# as14120_fpga_power_conf.net
KiCad netlist of a schematic drawn in Altium Designer
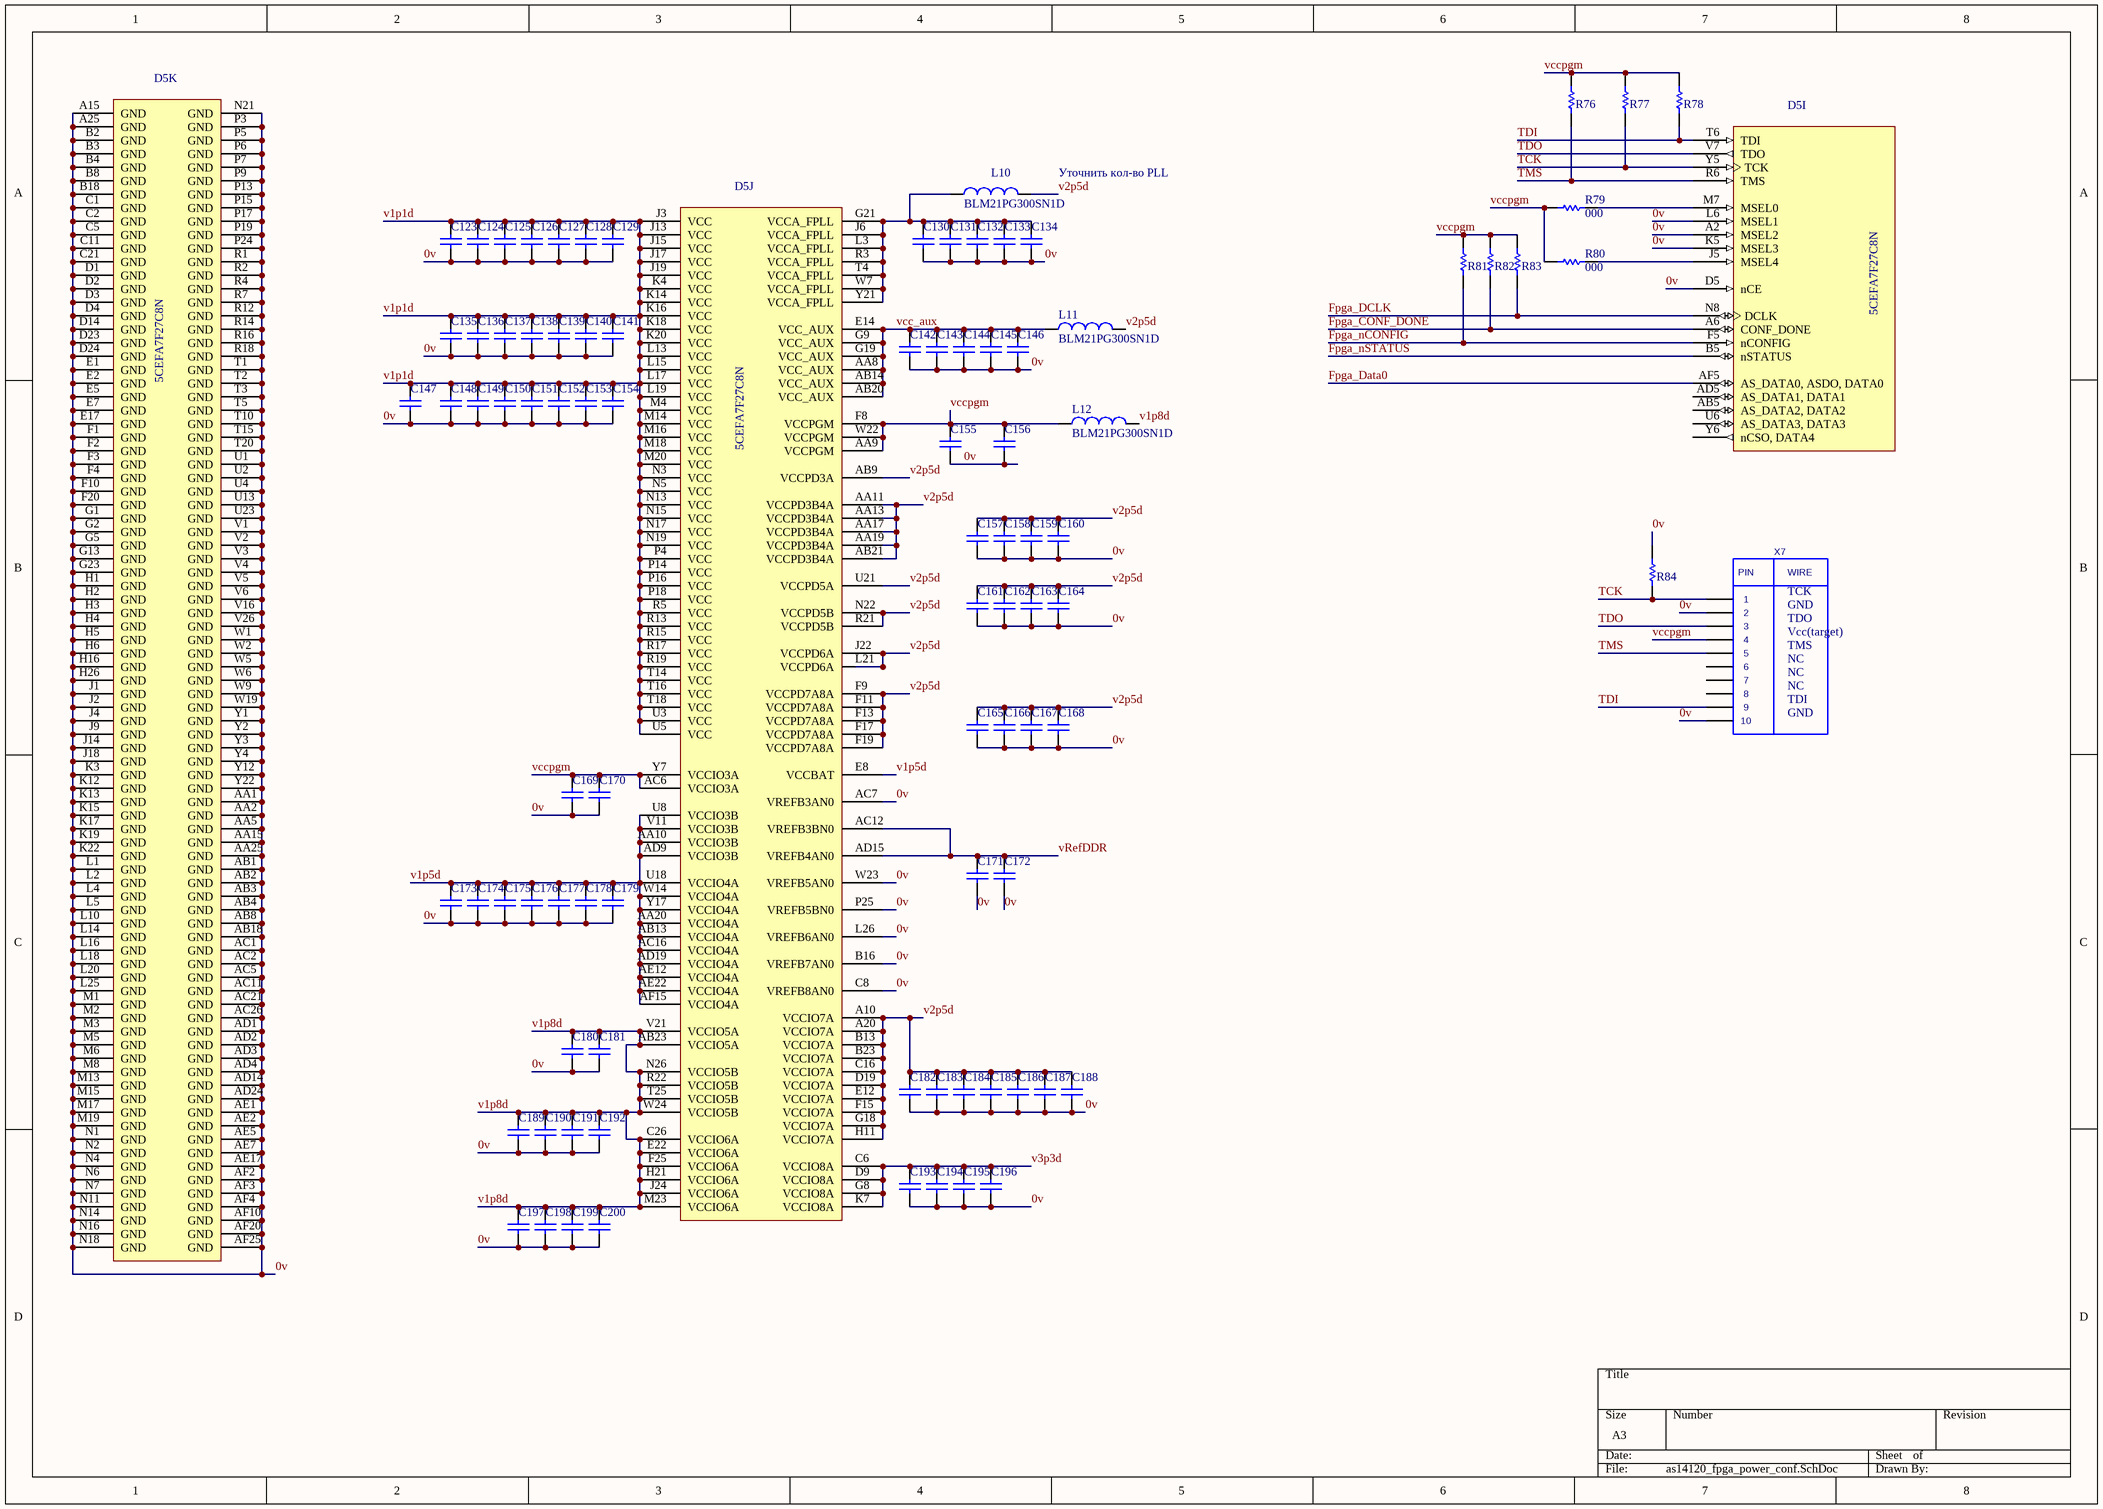
[diagram p0: as14120_fpga_power_conf.SchDoc]

(export (version "E")
  (design (tool "Eeschema 10.0.6"))
  (components
    (comp (ref "C123")
      (value "CAP 1uF 10V 0402(1005)")
      (footprint "CAPC0402(1005)60_M")
      (description "CAP 1uF 10V ±20% 0402 (1005 Metric) Thickness 0.6mm SMD")
      (fields (field (name "TOLERANCE") "±20%"))
      (libsource (lib "as14120") (part "CAP_0402"))
    )
    (comp (ref "C124")
      (value "CAP 1uF 10V 0402(1005)")
      (footprint "CAPC0402(1005)60_M")
      (description "CAP 1uF 10V ±20% 0402 (1005 Metric) Thickness 0.6mm SMD")
      (fields (field (name "TOLERANCE") "±20%"))
      (libsource (lib "as14120") (part "CAP_0402"))
    )
    (comp (ref "C125")
      (value "CAP 1uF 10V 0402(1005)")
      (footprint "CAPC0402(1005)60_M")
      (description "CAP 1uF 10V ±20% 0402 (1005 Metric) Thickness 0.6mm SMD")
      (fields (field (name "TOLERANCE") "±20%"))
      (libsource (lib "as14120") (part "CAP_0402"))
    )
    (comp (ref "C126")
      (value "CAP 1uF 10V 0402(1005)")
      (footprint "CAPC0402(1005)60_M")
      (description "CAP 1uF 10V ±20% 0402 (1005 Metric) Thickness 0.6mm SMD")
      (fields (field (name "TOLERANCE") "±20%"))
      (libsource (lib "as14120") (part "CAP_0402"))
    )
    (comp (ref "C127")
      (value "CAP 1uF 10V 0402(1005)")
      (footprint "CAPC0402(1005)60_M")
      (description "CAP 1uF 10V ±20% 0402 (1005 Metric) Thickness 0.6mm SMD")
      (fields (field (name "TOLERANCE") "±20%"))
      (libsource (lib "as14120") (part "CAP_0402"))
    )
    (comp (ref "C128")
      (value "CAP 1uF 10V 0402(1005)")
      (footprint "CAPC0402(1005)60_M")
      (description "CAP 1uF 10V ±20% 0402 (1005 Metric) Thickness 0.6mm SMD")
      (fields (field (name "TOLERANCE") "±20%"))
      (libsource (lib "as14120") (part "CAP_0402"))
    )
    (comp (ref "C129")
      (value "CAP 1uF 10V 0402(1005)")
      (footprint "CAPC0402(1005)60_M")
      (description "CAP 1uF 10V ±20% 0402 (1005 Metric) Thickness 0.6mm SMD")
      (fields (field (name "TOLERANCE") "±20%"))
      (libsource (lib "as14120") (part "CAP_0402"))
    )
    (comp (ref "C130")
      (value "CAP 1uF 10V 0402(1005)")
      (footprint "CAPC0402(1005)60_M")
      (description "CAP 1uF 10V ±20% 0402 (1005 Metric) Thickness 0.6mm SMD")
      (fields (field (name "TOLERANCE") "±20%"))
      (libsource (lib "as14120") (part "CAP_0402"))
    )
    (comp (ref "C131")
      (value "CAP 1uF 10V 0402(1005)")
      (footprint "CAPC0402(1005)60_M")
      (description "CAP 1uF 10V ±20% 0402 (1005 Metric) Thickness 0.6mm SMD")
      (fields (field (name "TOLERANCE") "±20%"))
      (libsource (lib "as14120") (part "CAP_0402"))
    )
    (comp (ref "C132")
      (value "CAP 1uF 10V 0402(1005)")
      (footprint "CAPC0402(1005)60_M")
      (description "CAP 1uF 10V ±20% 0402 (1005 Metric) Thickness 0.6mm SMD")
      (fields (field (name "TOLERANCE") "±20%"))
      (libsource (lib "as14120") (part "CAP_0402"))
    )
    (comp (ref "C133")
      (value "CAP 1uF 10V 0402(1005)")
      (footprint "CAPC0402(1005)60_M")
      (description "CAP 1uF 10V ±20% 0402 (1005 Metric) Thickness 0.6mm SMD")
      (fields (field (name "TOLERANCE") "±20%"))
      (libsource (lib "as14120") (part "CAP_0402"))
    )
    (comp (ref "C134")
      (value "CAP 1uF 10V 0402(1005)")
      (footprint "CAPC0402(1005)60_M")
      (description "CAP 1uF 10V ±20% 0402 (1005 Metric) Thickness 0.6mm SMD")
      (fields (field (name "TOLERANCE") "±20%"))
      (libsource (lib "as14120") (part "CAP_0402"))
    )
    (comp (ref "C135")
      (value "CAP 1uF 10V 0402(1005)")
      (footprint "CAPC0402(1005)60_M")
      (description "CAP 1uF 10V ±20% 0402 (1005 Metric) Thickness 0.6mm SMD")
      (fields (field (name "TOLERANCE") "±20%"))
      (libsource (lib "as14120") (part "CAP_0402"))
    )
    (comp (ref "C136")
      (value "CAP 1uF 10V 0402(1005)")
      (footprint "CAPC0402(1005)60_M")
      (description "CAP 1uF 10V ±20% 0402 (1005 Metric) Thickness 0.6mm SMD")
      (fields (field (name "TOLERANCE") "±20%"))
      (libsource (lib "as14120") (part "CAP_0402"))
    )
    (comp (ref "C137")
      (value "CAP 1uF 10V 0402(1005)")
      (footprint "CAPC0402(1005)60_M")
      (description "CAP 1uF 10V ±20% 0402 (1005 Metric) Thickness 0.6mm SMD")
      (fields (field (name "TOLERANCE") "±20%"))
      (libsource (lib "as14120") (part "CAP_0402"))
    )
    (comp (ref "C138")
      (value "CAP 1uF 10V 0402(1005)")
      (footprint "CAPC0402(1005)60_M")
      (description "CAP 1uF 10V ±20% 0402 (1005 Metric) Thickness 0.6mm SMD")
      (fields (field (name "TOLERANCE") "±20%"))
      (libsource (lib "as14120") (part "CAP_0402"))
    )
    (comp (ref "C139")
      (value "CAP 1uF 10V 0402(1005)")
      (footprint "CAPC0402(1005)60_M")
      (description "CAP 1uF 10V ±20% 0402 (1005 Metric) Thickness 0.6mm SMD")
      (fields (field (name "TOLERANCE") "±20%"))
      (libsource (lib "as14120") (part "CAP_0402"))
    )
    (comp (ref "C140")
      (value "CAP 1uF 10V 0402(1005)")
      (footprint "CAPC0402(1005)60_M")
      (description "CAP 1uF 10V ±20% 0402 (1005 Metric) Thickness 0.6mm SMD")
      (fields (field (name "TOLERANCE") "±20%"))
      (libsource (lib "as14120") (part "CAP_0402"))
    )
    (comp (ref "C141")
      (value "CAP 1uF 10V 0402(1005)")
      (footprint "CAPC0402(1005)60_M")
      (description "CAP 1uF 10V ±20% 0402 (1005 Metric) Thickness 0.6mm SMD")
      (fields (field (name "TOLERANCE") "±20%"))
      (libsource (lib "as14120") (part "CAP_0402"))
    )
    (comp (ref "C142")
      (value "CAP 1uF 10V 0402(1005)")
      (footprint "CAPC0402(1005)60_M")
      (description "CAP 1uF 10V ±20% 0402 (1005 Metric) Thickness 0.6mm SMD")
      (fields (field (name "TOLERANCE") "±20%"))
      (libsource (lib "as14120") (part "CAP_0402"))
    )
    (comp (ref "C143")
      (value "CAP 1uF 10V 0402(1005)")
      (footprint "CAPC0402(1005)60_M")
      (description "CAP 1uF 10V ±20% 0402 (1005 Metric) Thickness 0.6mm SMD")
      (fields (field (name "TOLERANCE") "±20%"))
      (libsource (lib "as14120") (part "CAP_0402"))
    )
    (comp (ref "C144")
      (value "CAP 1uF 10V 0402(1005)")
      (footprint "CAPC0402(1005)60_M")
      (description "CAP 1uF 10V ±20% 0402 (1005 Metric) Thickness 0.6mm SMD")
      (fields (field (name "TOLERANCE") "±20%"))
      (libsource (lib "as14120") (part "CAP_0402"))
    )
    (comp (ref "C145")
      (value "CAP 1uF 10V 0402(1005)")
      (footprint "CAPC0402(1005)60_M")
      (description "CAP 1uF 10V ±20% 0402 (1005 Metric) Thickness 0.6mm SMD")
      (fields (field (name "TOLERANCE") "±20%"))
      (libsource (lib "as14120") (part "CAP_0402"))
    )
    (comp (ref "C146")
      (value "CAP 1uF 10V 0402(1005)")
      (footprint "CAPC0402(1005)60_M")
      (description "CAP 1uF 10V ±20% 0402 (1005 Metric) Thickness 0.6mm SMD")
      (fields (field (name "TOLERANCE") "±20%"))
      (libsource (lib "as14120") (part "CAP_0402"))
    )
    (comp (ref "C147")
      (value "CAP 1uF 10V 0402(1005)")
      (footprint "CAPC0402(1005)60_M")
      (description "CAP 1uF 10V ±20% 0402 (1005 Metric) Thickness 0.6mm SMD")
      (fields (field (name "TOLERANCE") "±20%"))
      (libsource (lib "as14120") (part "CAP_0402"))
    )
    (comp (ref "C148")
      (value "CAP 1uF 10V 0402(1005)")
      (footprint "CAPC0402(1005)60_M")
      (description "CAP 1uF 10V ±20% 0402 (1005 Metric) Thickness 0.6mm SMD")
      (fields (field (name "TOLERANCE") "±20%"))
      (libsource (lib "as14120") (part "CAP_0402"))
    )
    (comp (ref "C149")
      (value "CAP 1uF 10V 0402(1005)")
      (footprint "CAPC0402(1005)60_M")
      (description "CAP 1uF 10V ±20% 0402 (1005 Metric) Thickness 0.6mm SMD")
      (fields (field (name "TOLERANCE") "±20%"))
      (libsource (lib "as14120") (part "CAP_0402"))
    )
    (comp (ref "C150")
      (value "CAP 1uF 10V 0402(1005)")
      (footprint "CAPC0402(1005)60_M")
      (description "CAP 1uF 10V ±20% 0402 (1005 Metric) Thickness 0.6mm SMD")
      (fields (field (name "TOLERANCE") "±20%"))
      (libsource (lib "as14120") (part "CAP_0402"))
    )
    (comp (ref "C151")
      (value "CAP 1uF 10V 0402(1005)")
      (footprint "CAPC0402(1005)60_M")
      (description "CAP 1uF 10V ±20% 0402 (1005 Metric) Thickness 0.6mm SMD")
      (fields (field (name "TOLERANCE") "±20%"))
      (libsource (lib "as14120") (part "CAP_0402"))
    )
    (comp (ref "C152")
      (value "CAP 1uF 10V 0402(1005)")
      (footprint "CAPC0402(1005)60_M")
      (description "CAP 1uF 10V ±20% 0402 (1005 Metric) Thickness 0.6mm SMD")
      (fields (field (name "TOLERANCE") "±20%"))
      (libsource (lib "as14120") (part "CAP_0402"))
    )
    (comp (ref "C153")
      (value "CAP 1uF 10V 0402(1005)")
      (footprint "CAPC0402(1005)60_M")
      (description "CAP 1uF 10V ±20% 0402 (1005 Metric) Thickness 0.6mm SMD")
      (fields (field (name "TOLERANCE") "±20%"))
      (libsource (lib "as14120") (part "CAP_0402"))
    )
    (comp (ref "C154")
      (value "CAP 1uF 10V 0402(1005)")
      (footprint "CAPC0402(1005)60_M")
      (description "CAP 1uF 10V ±20% 0402 (1005 Metric) Thickness 0.6mm SMD")
      (fields (field (name "TOLERANCE") "±20%"))
      (libsource (lib "as14120") (part "CAP_0402"))
    )
    (comp (ref "C155")
      (value "CAP 1uF 10V 0402(1005)")
      (footprint "CAPC0402(1005)60_M")
      (description "CAP 1uF 10V ±20% 0402 (1005 Metric) Thickness 0.6mm SMD")
      (fields (field (name "TOLERANCE") "±20%"))
      (libsource (lib "as14120") (part "CAP_0402"))
    )
    (comp (ref "C156")
      (value "CAP 1uF 10V 0402(1005)")
      (footprint "CAPC0402(1005)60_M")
      (description "CAP 1uF 10V ±20% 0402 (1005 Metric) Thickness 0.6mm SMD")
      (fields (field (name "TOLERANCE") "±20%"))
      (libsource (lib "as14120") (part "CAP_0402"))
    )
    (comp (ref "C157")
      (value "CAP 1uF 10V 0402(1005)")
      (footprint "CAPC0402(1005)60_M")
      (description "CAP 1uF 10V ±20% 0402 (1005 Metric) Thickness 0.6mm SMD")
      (fields (field (name "TOLERANCE") "±20%"))
      (libsource (lib "as14120") (part "CAP_0402"))
    )
    (comp (ref "C158")
      (value "CAP 1uF 10V 0402(1005)")
      (footprint "CAPC0402(1005)60_M")
      (description "CAP 1uF 10V ±20% 0402 (1005 Metric) Thickness 0.6mm SMD")
      (fields (field (name "TOLERANCE") "±20%"))
      (libsource (lib "as14120") (part "CAP_0402"))
    )
    (comp (ref "C159")
      (value "CAP 1uF 10V 0402(1005)")
      (footprint "CAPC0402(1005)60_M")
      (description "CAP 1uF 10V ±20% 0402 (1005 Metric) Thickness 0.6mm SMD")
      (fields (field (name "TOLERANCE") "±20%"))
      (libsource (lib "as14120") (part "CAP_0402"))
    )
    (comp (ref "C160")
      (value "CAP 1uF 10V 0402(1005)")
      (footprint "CAPC0402(1005)60_M")
      (description "CAP 1uF 10V ±20% 0402 (1005 Metric) Thickness 0.6mm SMD")
      (fields (field (name "TOLERANCE") "±20%"))
      (libsource (lib "as14120") (part "CAP_0402"))
    )
    (comp (ref "C161")
      (value "CAP 1uF 10V 0402(1005)")
      (footprint "CAPC0402(1005)60_M")
      (description "CAP 1uF 10V ±20% 0402 (1005 Metric) Thickness 0.6mm SMD")
      (fields (field (name "TOLERANCE") "±20%"))
      (libsource (lib "as14120") (part "CAP_0402"))
    )
    (comp (ref "C162")
      (value "CAP 1uF 10V 0402(1005)")
      (footprint "CAPC0402(1005)60_M")
      (description "CAP 1uF 10V ±20% 0402 (1005 Metric) Thickness 0.6mm SMD")
      (fields (field (name "TOLERANCE") "±20%"))
      (libsource (lib "as14120") (part "CAP_0402"))
    )
    (comp (ref "C163")
      (value "CAP 1uF 10V 0402(1005)")
      (footprint "CAPC0402(1005)60_M")
      (description "CAP 1uF 10V ±20% 0402 (1005 Metric) Thickness 0.6mm SMD")
      (fields (field (name "TOLERANCE") "±20%"))
      (libsource (lib "as14120") (part "CAP_0402"))
    )
    (comp (ref "C164")
      (value "CAP 1uF 10V 0402(1005)")
      (footprint "CAPC0402(1005)60_M")
      (description "CAP 1uF 10V ±20% 0402 (1005 Metric) Thickness 0.6mm SMD")
      (fields (field (name "TOLERANCE") "±20%"))
      (libsource (lib "as14120") (part "CAP_0402"))
    )
    (comp (ref "C165")
      (value "CAP 1uF 10V 0402(1005)")
      (footprint "CAPC0402(1005)60_M")
      (description "CAP 1uF 10V ±20% 0402 (1005 Metric) Thickness 0.6mm SMD")
      (fields (field (name "TOLERANCE") "±20%"))
      (libsource (lib "as14120") (part "CAP_0402"))
    )
    (comp (ref "C166")
      (value "CAP 1uF 10V 0402(1005)")
      (footprint "CAPC0402(1005)60_M")
      (description "CAP 1uF 10V ±20% 0402 (1005 Metric) Thickness 0.6mm SMD")
      (fields (field (name "TOLERANCE") "±20%"))
      (libsource (lib "as14120") (part "CAP_0402"))
    )
    (comp (ref "C167")
      (value "CAP 1uF 10V 0402(1005)")
      (footprint "CAPC0402(1005)60_M")
      (description "CAP 1uF 10V ±20% 0402 (1005 Metric) Thickness 0.6mm SMD")
      (fields (field (name "TOLERANCE") "±20%"))
      (libsource (lib "as14120") (part "CAP_0402"))
    )
    (comp (ref "C168")
      (value "CAP 1uF 10V 0402(1005)")
      (footprint "CAPC0402(1005)60_M")
      (description "CAP 1uF 10V ±20% 0402 (1005 Metric) Thickness 0.6mm SMD")
      (fields (field (name "TOLERANCE") "±20%"))
      (libsource (lib "as14120") (part "CAP_0402"))
    )
    (comp (ref "C169")
      (value "CAP 1uF 10V 0402(1005)")
      (footprint "CAPC0402(1005)60_M")
      (description "CAP 1uF 10V ±20% 0402 (1005 Metric) Thickness 0.6mm SMD")
      (fields (field (name "TOLERANCE") "±20%"))
      (libsource (lib "as14120") (part "CAP_0402"))
    )
    (comp (ref "C170")
      (value "CAP 1uF 10V 0402(1005)")
      (footprint "CAPC0402(1005)60_M")
      (description "CAP 1uF 10V ±20% 0402 (1005 Metric) Thickness 0.6mm SMD")
      (fields (field (name "TOLERANCE") "±20%"))
      (libsource (lib "as14120") (part "CAP_0402"))
    )
    (comp (ref "C171")
      (value "CAP 1uF 10V 0402(1005)")
      (footprint "CAPC0402(1005)60_M")
      (description "CAP 1uF 10V ±20% 0402 (1005 Metric) Thickness 0.6mm SMD")
      (fields (field (name "TOLERANCE") "±20%"))
      (libsource (lib "as14120") (part "CAP_0402"))
    )
    (comp (ref "C172")
      (value "CAP 1uF 10V 0402(1005)")
      (footprint "CAPC0402(1005)60_M")
      (description "CAP 1uF 10V ±20% 0402 (1005 Metric) Thickness 0.6mm SMD")
      (fields (field (name "TOLERANCE") "±20%"))
      (libsource (lib "as14120") (part "CAP_0402"))
    )
    (comp (ref "C173")
      (value "CAP 1uF 10V 0402(1005)")
      (footprint "CAPC0402(1005)60_M")
      (description "CAP 1uF 10V ±20% 0402 (1005 Metric) Thickness 0.6mm SMD")
      (fields (field (name "TOLERANCE") "±20%"))
      (libsource (lib "as14120") (part "CAP_0402"))
    )
    (comp (ref "C174")
      (value "CAP 1uF 10V 0402(1005)")
      (footprint "CAPC0402(1005)60_M")
      (description "CAP 1uF 10V ±20% 0402 (1005 Metric) Thickness 0.6mm SMD")
      (fields (field (name "TOLERANCE") "±20%"))
      (libsource (lib "as14120") (part "CAP_0402"))
    )
    (comp (ref "C175")
      (value "CAP 1uF 10V 0402(1005)")
      (footprint "CAPC0402(1005)60_M")
      (description "CAP 1uF 10V ±20% 0402 (1005 Metric) Thickness 0.6mm SMD")
      (fields (field (name "TOLERANCE") "±20%"))
      (libsource (lib "as14120") (part "CAP_0402"))
    )
    (comp (ref "C176")
      (value "CAP 1uF 10V 0402(1005)")
      (footprint "CAPC0402(1005)60_M")
      (description "CAP 1uF 10V ±20% 0402 (1005 Metric) Thickness 0.6mm SMD")
      (fields (field (name "TOLERANCE") "±20%"))
      (libsource (lib "as14120") (part "CAP_0402"))
    )
    (comp (ref "C177")
      (value "CAP 1uF 10V 0402(1005)")
      (footprint "CAPC0402(1005)60_M")
      (description "CAP 1uF 10V ±20% 0402 (1005 Metric) Thickness 0.6mm SMD")
      (fields (field (name "TOLERANCE") "±20%"))
      (libsource (lib "as14120") (part "CAP_0402"))
    )
    (comp (ref "C178")
      (value "CAP 1uF 10V 0402(1005)")
      (footprint "CAPC0402(1005)60_M")
      (description "CAP 1uF 10V ±20% 0402 (1005 Metric) Thickness 0.6mm SMD")
      (fields (field (name "TOLERANCE") "±20%"))
      (libsource (lib "as14120") (part "CAP_0402"))
    )
    (comp (ref "C179")
      (value "CAP 1uF 10V 0402(1005)")
      (footprint "CAPC0402(1005)60_M")
      (description "CAP 1uF 10V ±20% 0402 (1005 Metric) Thickness 0.6mm SMD")
      (fields (field (name "TOLERANCE") "±20%"))
      (libsource (lib "as14120") (part "CAP_0402"))
    )
    (comp (ref "C180")
      (value "CAP 1uF 10V 0402(1005)")
      (footprint "CAPC0402(1005)60_M")
      (description "CAP 1uF 10V ±20% 0402 (1005 Metric) Thickness 0.6mm SMD")
      (fields (field (name "TOLERANCE") "±20%"))
      (libsource (lib "as14120") (part "CAP_0402"))
    )
    (comp (ref "C181")
      (value "CAP 1uF 10V 0402(1005)")
      (footprint "CAPC0402(1005)60_M")
      (description "CAP 1uF 10V ±20% 0402 (1005 Metric) Thickness 0.6mm SMD")
      (fields (field (name "TOLERANCE") "±20%"))
      (libsource (lib "as14120") (part "CAP_0402"))
    )
    (comp (ref "C182")
      (value "CAP 1uF 10V 0402(1005)")
      (footprint "CAPC0402(1005)60_M")
      (description "CAP 1uF 10V ±20% 0402 (1005 Metric) Thickness 0.6mm SMD")
      (fields (field (name "TOLERANCE") "±20%"))
      (libsource (lib "as14120") (part "CAP_0402"))
    )
    (comp (ref "C183")
      (value "CAP 1uF 10V 0402(1005)")
      (footprint "CAPC0402(1005)60_M")
      (description "CAP 1uF 10V ±20% 0402 (1005 Metric) Thickness 0.6mm SMD")
      (fields (field (name "TOLERANCE") "±20%"))
      (libsource (lib "as14120") (part "CAP_0402"))
    )
    (comp (ref "C184")
      (value "CAP 1uF 10V 0402(1005)")
      (footprint "CAPC0402(1005)60_M")
      (description "CAP 1uF 10V ±20% 0402 (1005 Metric) Thickness 0.6mm SMD")
      (fields (field (name "TOLERANCE") "±20%"))
      (libsource (lib "as14120") (part "CAP_0402"))
    )
    (comp (ref "C185")
      (value "CAP 1uF 10V 0402(1005)")
      (footprint "CAPC0402(1005)60_M")
      (description "CAP 1uF 10V ±20% 0402 (1005 Metric) Thickness 0.6mm SMD")
      (fields (field (name "TOLERANCE") "±20%"))
      (libsource (lib "as14120") (part "CAP_0402"))
    )
    (comp (ref "C186")
      (value "CAP 1uF 10V 0402(1005)")
      (footprint "CAPC0402(1005)60_M")
      (description "CAP 1uF 10V ±20% 0402 (1005 Metric) Thickness 0.6mm SMD")
      (fields (field (name "TOLERANCE") "±20%"))
      (libsource (lib "as14120") (part "CAP_0402"))
    )
    (comp (ref "C187")
      (value "CAP 1uF 10V 0402(1005)")
      (footprint "CAPC0402(1005)60_M")
      (description "CAP 1uF 10V ±20% 0402 (1005 Metric) Thickness 0.6mm SMD")
      (fields (field (name "TOLERANCE") "±20%"))
      (libsource (lib "as14120") (part "CAP_0402"))
    )
    (comp (ref "C188")
      (value "CAP 1uF 10V 0402(1005)")
      (footprint "CAPC0402(1005)60_M")
      (description "CAP 1uF 10V ±20% 0402 (1005 Metric) Thickness 0.6mm SMD")
      (fields (field (name "TOLERANCE") "±20%"))
      (libsource (lib "as14120") (part "CAP_0402"))
    )
    (comp (ref "C189")
      (value "CAP 1uF 10V 0402(1005)")
      (footprint "CAPC0402(1005)60_M")
      (description "CAP 1uF 10V ±20% 0402 (1005 Metric) Thickness 0.6mm SMD")
      (fields (field (name "TOLERANCE") "±20%"))
      (libsource (lib "as14120") (part "CAP_0402"))
    )
    (comp (ref "C190")
      (value "CAP 1uF 10V 0402(1005)")
      (footprint "CAPC0402(1005)60_M")
      (description "CAP 1uF 10V ±20% 0402 (1005 Metric) Thickness 0.6mm SMD")
      (fields (field (name "TOLERANCE") "±20%"))
      (libsource (lib "as14120") (part "CAP_0402"))
    )
    (comp (ref "C191")
      (value "CAP 1uF 10V 0402(1005)")
      (footprint "CAPC0402(1005)60_M")
      (description "CAP 1uF 10V ±20% 0402 (1005 Metric) Thickness 0.6mm SMD")
      (fields (field (name "TOLERANCE") "±20%"))
      (libsource (lib "as14120") (part "CAP_0402"))
    )
    (comp (ref "C192")
      (value "CAP 1uF 10V 0402(1005)")
      (footprint "CAPC0402(1005)60_M")
      (description "CAP 1uF 10V ±20% 0402 (1005 Metric) Thickness 0.6mm SMD")
      (fields (field (name "TOLERANCE") "±20%"))
      (libsource (lib "as14120") (part "CAP_0402"))
    )
    (comp (ref "C193")
      (value "CAP 1uF 10V 0402(1005)")
      (footprint "CAPC0402(1005)60_M")
      (description "CAP 1uF 10V ±20% 0402 (1005 Metric) Thickness 0.6mm SMD")
      (fields (field (name "TOLERANCE") "±20%"))
      (libsource (lib "as14120") (part "CAP_0402"))
    )
    (comp (ref "C194")
      (value "CAP 1uF 10V 0402(1005)")
      (footprint "CAPC0402(1005)60_M")
      (description "CAP 1uF 10V ±20% 0402 (1005 Metric) Thickness 0.6mm SMD")
      (fields (field (name "TOLERANCE") "±20%"))
      (libsource (lib "as14120") (part "CAP_0402"))
    )
    (comp (ref "C195")
      (value "CAP 1uF 10V 0402(1005)")
      (footprint "CAPC0402(1005)60_M")
      (description "CAP 1uF 10V ±20% 0402 (1005 Metric) Thickness 0.6mm SMD")
      (fields (field (name "TOLERANCE") "±20%"))
      (libsource (lib "as14120") (part "CAP_0402"))
    )
    (comp (ref "C196")
      (value "CAP 1uF 10V 0402(1005)")
      (footprint "CAPC0402(1005)60_M")
      (description "CAP 1uF 10V ±20% 0402 (1005 Metric) Thickness 0.6mm SMD")
      (fields (field (name "TOLERANCE") "±20%"))
      (libsource (lib "as14120") (part "CAP_0402"))
    )
    (comp (ref "C197")
      (value "CAP 1uF 10V 0402(1005)")
      (footprint "CAPC0402(1005)60_M")
      (description "CAP 1uF 10V ±20% 0402 (1005 Metric) Thickness 0.6mm SMD")
      (fields (field (name "TOLERANCE") "±20%"))
      (libsource (lib "as14120") (part "CAP_0402"))
    )
    (comp (ref "C198")
      (value "CAP 1uF 10V 0402(1005)")
      (footprint "CAPC0402(1005)60_M")
      (description "CAP 1uF 10V ±20% 0402 (1005 Metric) Thickness 0.6mm SMD")
      (fields (field (name "TOLERANCE") "±20%"))
      (libsource (lib "as14120") (part "CAP_0402"))
    )
    (comp (ref "C199")
      (value "CAP 1uF 10V 0402(1005)")
      (footprint "CAPC0402(1005)60_M")
      (description "CAP 1uF 10V ±20% 0402 (1005 Metric) Thickness 0.6mm SMD")
      (fields (field (name "TOLERANCE") "±20%"))
      (libsource (lib "as14120") (part "CAP_0402"))
    )
    (comp (ref "C200")
      (value "CAP 1uF 10V 0402(1005)")
      (footprint "CAPC0402(1005)60_M")
      (description "CAP 1uF 10V ±20% 0402 (1005 Metric) Thickness 0.6mm SMD")
      (fields (field (name "TOLERANCE") "±20%"))
      (libsource (lib "as14120") (part "CAP_0402"))
    )
    (comp (ref "D5")
      (value "5CEFA7F27C8N")
      (footprint "ALTR-672-FBGA-2000A")
      (fields (field (name "MANUFACTURER") "Altera"))
      (libsource (lib "Altera Cyclone V E") (part "5CEFA7F27C8N"))
    )
    (comp (ref "L10")
      (value "BLM21PG300SN1D")
      (footprint "CAPC0805(2012)100_N")
      (libsource (lib "as14120") (part "Ferrite_beat"))
    )
    (comp (ref "L11")
      (value "BLM21PG300SN1D")
      (footprint "CAPC0805(2012)100_N")
      (libsource (lib "as14120") (part "Ferrite_beat"))
    )
    (comp (ref "L12")
      (value "BLM21PG300SN1D")
      (footprint "CAPC0805(2012)100_N")
      (libsource (lib "as14120") (part "Ferrite_beat"))
    )
    (comp (ref "R76")
      (value "1K 5% 0603(1608)")
      (footprint "RESC0603(1608)_L")
      (description "1K 0.1W 5% 0603 (1608 Metric)  SMD")
      (fields (field (name "TOLERANCE") "5 %") (field (name "POWER") "0.1 W"))
      (libsource (lib "as14120") (part "RES_0603"))
    )
    (comp (ref "R77")
      (value "1K 5% 0603(1608)")
      (footprint "RESC0603(1608)_L")
      (description "1K 0.1W 5% 0603 (1608 Metric)  SMD")
      (fields (field (name "TOLERANCE") "5 %") (field (name "POWER") "0.1 W"))
      (libsource (lib "as14120") (part "RES_0603"))
    )
    (comp (ref "R78")
      (value "1K 5% 0603(1608)")
      (footprint "RESC0603(1608)_L")
      (description "1K 0.1W 5% 0603 (1608 Metric)  SMD")
      (fields (field (name "TOLERANCE") "5 %") (field (name "POWER") "0.1 W"))
      (libsource (lib "as14120") (part "RES_0603"))
    )
    (comp (ref "R79")
      (value "000")
      (footprint "RESC0603(1608)_L")
      (description "1K 0.1W 5% 0603 (1608 Metric)  SMD")
      (fields (field (name "TOLERANCE") "5 %") (field (name "POWER") "0.1 W"))
      (libsource (lib "as14120") (part "RES_0603"))
    )
    (comp (ref "R80")
      (value "000")
      (footprint "RESC0603(1608)_L")
      (description "1K 0.1W 5% 0603 (1608 Metric)  SMD")
      (fields (field (name "TOLERANCE") "5 %") (field (name "POWER") "0.1 W"))
      (libsource (lib "as14120") (part "RES_0603"))
    )
    (comp (ref "R81")
      (value "1K 5% 0603(1608)")
      (footprint "RESC0603(1608)_L")
      (description "1K 0.1W 5% 0603 (1608 Metric)  SMD")
      (fields (field (name "TOLERANCE") "5 %") (field (name "POWER") "0.1 W"))
      (libsource (lib "as14120") (part "RES_0603"))
    )
    (comp (ref "R82")
      (value "1K 5% 0603(1608)")
      (footprint "RESC0603(1608)_L")
      (description "1K 0.1W 5% 0603 (1608 Metric)  SMD")
      (fields (field (name "TOLERANCE") "5 %") (field (name "POWER") "0.1 W"))
      (libsource (lib "as14120") (part "RES_0603"))
    )
    (comp (ref "R83")
      (value "1K 5% 0603(1608)")
      (footprint "RESC0603(1608)_L")
      (description "1K 0.1W 5% 0603 (1608 Metric)  SMD")
      (fields (field (name "TOLERANCE") "5 %") (field (name "POWER") "0.1 W"))
      (libsource (lib "as14120") (part "RES_0603"))
    )
    (comp (ref "R84")
      (value "1K 5% 0603(1608)")
      (footprint "RESC0603(1608)_L")
      (description "1K 0.1W 5% 0603 (1608 Metric)  SMD")
      (fields (field (name "TOLERANCE") "5 %") (field (name "POWER") "0.1 W"))
      (libsource (lib "as14120") (part "RES_0603"))
    )
    (comp (ref "X7") (value "IDC10") (footprint "IDC10M") (libsource (lib "alexsb") (part "IDC10")))
  )
  (nets
    (net (code "1") (name "/0v") (class "Default")
      (node (ref "C123") (pin "1") (pinfunction "1_1") (pintype "passive"))
      (node (ref "C124") (pin "1") (pinfunction "1_1") (pintype "passive"))
      (node (ref "C125") (pin "1") (pinfunction "1_1") (pintype "passive"))
      (node (ref "C126") (pin "1") (pinfunction "1_1") (pintype "passive"))
      (node (ref "C127") (pin "1") (pinfunction "1_1") (pintype "passive"))
      (node (ref "C128") (pin "1") (pinfunction "1_1") (pintype "passive"))
      (node (ref "C129") (pin "1") (pinfunction "1_1") (pintype "passive"))
      (node (ref "C130") (pin "1") (pinfunction "1_1") (pintype "passive"))
      (node (ref "C131") (pin "1") (pinfunction "1_1") (pintype "passive"))
      (node (ref "C132") (pin "1") (pinfunction "1_1") (pintype "passive"))
      (node (ref "C133") (pin "1") (pinfunction "1_1") (pintype "passive"))
      (node (ref "C134") (pin "1") (pinfunction "1_1") (pintype "passive"))
      (node (ref "C135") (pin "1") (pinfunction "1_1") (pintype "passive"))
      (node (ref "C136") (pin "1") (pinfunction "1_1") (pintype "passive"))
      (node (ref "C137") (pin "1") (pinfunction "1_1") (pintype "passive"))
      (node (ref "C138") (pin "1") (pinfunction "1_1") (pintype "passive"))
      (node (ref "C139") (pin "1") (pinfunction "1_1") (pintype "passive"))
      (node (ref "C140") (pin "1") (pinfunction "1_1") (pintype "passive"))
      (node (ref "C141") (pin "1") (pinfunction "1_1") (pintype "passive"))
      (node (ref "C142") (pin "1") (pinfunction "1_1") (pintype "passive"))
      (node (ref "C143") (pin "1") (pinfunction "1_1") (pintype "passive"))
      (node (ref "C144") (pin "1") (pinfunction "1_1") (pintype "passive"))
      (node (ref "C145") (pin "1") (pinfunction "1_1") (pintype "passive"))
      (node (ref "C146") (pin "1") (pinfunction "1_1") (pintype "passive"))
      (node (ref "C147") (pin "1") (pinfunction "1_1") (pintype "passive"))
      (node (ref "C148") (pin "1") (pinfunction "1_1") (pintype "passive"))
      (node (ref "C149") (pin "1") (pinfunction "1_1") (pintype "passive"))
      (node (ref "C150") (pin "1") (pinfunction "1_1") (pintype "passive"))
      (node (ref "C151") (pin "1") (pinfunction "1_1") (pintype "passive"))
      (node (ref "C152") (pin "1") (pinfunction "1_1") (pintype "passive"))
      (node (ref "C153") (pin "1") (pinfunction "1_1") (pintype "passive"))
      (node (ref "C154") (pin "1") (pinfunction "1_1") (pintype "passive"))
      (node (ref "C155") (pin "1") (pinfunction "1_1") (pintype "passive"))
      (node (ref "C156") (pin "1") (pinfunction "1_1") (pintype "passive"))
      (node (ref "C157") (pin "1") (pinfunction "1_1") (pintype "passive"))
      (node (ref "C158") (pin "1") (pinfunction "1_1") (pintype "passive"))
      (node (ref "C159") (pin "1") (pinfunction "1_1") (pintype "passive"))
      (node (ref "C160") (pin "1") (pinfunction "1_1") (pintype "passive"))
      (node (ref "C161") (pin "1") (pinfunction "1_1") (pintype "passive"))
      (node (ref "C162") (pin "1") (pinfunction "1_1") (pintype "passive"))
      (node (ref "C163") (pin "1") (pinfunction "1_1") (pintype "passive"))
      (node (ref "C164") (pin "1") (pinfunction "1_1") (pintype "passive"))
      (node (ref "C165") (pin "1") (pinfunction "1_1") (pintype "passive"))
      (node (ref "C166") (pin "1") (pinfunction "1_1") (pintype "passive"))
      (node (ref "C167") (pin "1") (pinfunction "1_1") (pintype "passive"))
      (node (ref "C168") (pin "1") (pinfunction "1_1") (pintype "passive"))
      (node (ref "C169") (pin "1") (pinfunction "1_1") (pintype "passive"))
      (node (ref "C170") (pin "1") (pinfunction "1_1") (pintype "passive"))
      (node (ref "C171") (pin "1") (pinfunction "1_1") (pintype "passive"))
      (node (ref "C172") (pin "1") (pinfunction "1_1") (pintype "passive"))
      (node (ref "C173") (pin "1") (pinfunction "1_1") (pintype "passive"))
      (node (ref "C174") (pin "1") (pinfunction "1_1") (pintype "passive"))
      (node (ref "C175") (pin "1") (pinfunction "1_1") (pintype "passive"))
      (node (ref "C176") (pin "1") (pinfunction "1_1") (pintype "passive"))
      (node (ref "C177") (pin "1") (pinfunction "1_1") (pintype "passive"))
      (node (ref "C178") (pin "1") (pinfunction "1_1") (pintype "passive"))
      (node (ref "C179") (pin "1") (pinfunction "1_1") (pintype "passive"))
      (node (ref "C180") (pin "1") (pinfunction "1_1") (pintype "passive"))
      (node (ref "C181") (pin "1") (pinfunction "1_1") (pintype "passive"))
      (node (ref "C182") (pin "1") (pinfunction "1_1") (pintype "passive"))
      (node (ref "C183") (pin "1") (pinfunction "1_1") (pintype "passive"))
      (node (ref "C184") (pin "1") (pinfunction "1_1") (pintype "passive"))
      (node (ref "C185") (pin "1") (pinfunction "1_1") (pintype "passive"))
      (node (ref "C186") (pin "1") (pinfunction "1_1") (pintype "passive"))
      (node (ref "C187") (pin "1") (pinfunction "1_1") (pintype "passive"))
      (node (ref "C188") (pin "1") (pinfunction "1_1") (pintype "passive"))
      (node (ref "C189") (pin "1") (pinfunction "1_1") (pintype "passive"))
      (node (ref "C190") (pin "1") (pinfunction "1_1") (pintype "passive"))
      (node (ref "C191") (pin "1") (pinfunction "1_1") (pintype "passive"))
      (node (ref "C192") (pin "1") (pinfunction "1_1") (pintype "passive"))
      (node (ref "C193") (pin "1") (pinfunction "1_1") (pintype "passive"))
      (node (ref "C194") (pin "1") (pinfunction "1_1") (pintype "passive"))
      (node (ref "C195") (pin "1") (pinfunction "1_1") (pintype "passive"))
      (node (ref "C196") (pin "1") (pinfunction "1_1") (pintype "passive"))
      (node (ref "C197") (pin "1") (pinfunction "1_1") (pintype "passive"))
      (node (ref "C198") (pin "1") (pinfunction "1_1") (pintype "passive"))
      (node (ref "C199") (pin "1") (pinfunction "1_1") (pintype "passive"))
      (node (ref "C200") (pin "1") (pinfunction "1_1") (pintype "passive"))
      (node (ref "D5") (pin "A15") (pinfunction "GND_A15") (pintype "power_in"))
      (node (ref "D5") (pin "A2") (pinfunction "MSEL2_A2") (pintype "input"))
      (node (ref "D5") (pin "A25") (pinfunction "GND_A25") (pintype "power_in"))
      (node (ref "D5") (pin "AA1") (pinfunction "GND_AA1") (pintype "power_in"))
      (node (ref "D5") (pin "AA15") (pinfunction "GND_AA15") (pintype "power_in"))
      (node (ref "D5") (pin "AA2") (pinfunction "GND_AA2") (pintype "power_in"))
      (node (ref "D5") (pin "AA25") (pinfunction "GND_AA25") (pintype "power_in"))
      (node (ref "D5") (pin "AA5") (pinfunction "GND_AA5") (pintype "power_in"))
      (node (ref "D5") (pin "AB1") (pinfunction "GND_AB1") (pintype "power_in"))
      (node (ref "D5") (pin "AB18") (pinfunction "GND_AB18") (pintype "power_in"))
      (node (ref "D5") (pin "AB2") (pinfunction "GND_AB2") (pintype "power_in"))
      (node (ref "D5") (pin "AB3") (pinfunction "GND_AB3") (pintype "power_in"))
      (node (ref "D5") (pin "AB4") (pinfunction "GND_AB4") (pintype "power_in"))
      (node (ref "D5") (pin "AB8") (pinfunction "GND_AB8") (pintype "power_in"))
      (node (ref "D5") (pin "AC1") (pinfunction "GND_AC1") (pintype "power_in"))
      (node (ref "D5") (pin "AC11") (pinfunction "GND_AC11") (pintype "power_in"))
      (node (ref "D5") (pin "AC2") (pinfunction "GND_AC2") (pintype "power_in"))
      (node (ref "D5") (pin "AC21") (pinfunction "GND_AC21") (pintype "power_in"))
      (node (ref "D5") (pin "AC26") (pinfunction "GND_AC26") (pintype "power_in"))
      (node (ref "D5") (pin "AC5") (pinfunction "GND_AC5") (pintype "power_in"))
      (node (ref "D5") (pin "AC7") (pinfunction "VREFB3AN0_AC7") (pintype "power_in"))
      (node (ref "D5") (pin "AD1") (pinfunction "GND_AD1") (pintype "power_in"))
      (node (ref "D5") (pin "AD14") (pinfunction "GND_AD14") (pintype "power_in"))
      (node (ref "D5") (pin "AD2") (pinfunction "GND_AD2") (pintype "power_in"))
      (node (ref "D5") (pin "AD24") (pinfunction "GND_AD24") (pintype "power_in"))
      (node (ref "D5") (pin "AD3") (pinfunction "GND_AD3") (pintype "power_in"))
      (node (ref "D5") (pin "AD4") (pinfunction "GND_AD4") (pintype "power_in"))
      (node (ref "D5") (pin "AE1") (pinfunction "GND_AE1") (pintype "power_in"))
      (node (ref "D5") (pin "AE17") (pinfunction "GND_AE17") (pintype "power_in"))
      (node (ref "D5") (pin "AE2") (pinfunction "GND_AE2") (pintype "power_in"))
      (node (ref "D5") (pin "AE5") (pinfunction "GND_AE5") (pintype "power_in"))
      (node (ref "D5") (pin "AE7") (pinfunction "GND_AE7") (pintype "power_in"))
      (node (ref "D5") (pin "AF10") (pinfunction "GND_AF10") (pintype "power_in"))
      (node (ref "D5") (pin "AF2") (pinfunction "GND_AF2") (pintype "power_in"))
      (node (ref "D5") (pin "AF20") (pinfunction "GND_AF20") (pintype "power_in"))
      (node (ref "D5") (pin "AF25") (pinfunction "GND_AF25") (pintype "power_in"))
      (node (ref "D5") (pin "AF3") (pinfunction "GND_AF3") (pintype "power_in"))
      (node (ref "D5") (pin "AF4") (pinfunction "GND_AF4") (pintype "power_in"))
      (node (ref "D5") (pin "B16") (pinfunction "VREFB7AN0_B16") (pintype "power_in"))
      (node (ref "D5") (pin "B18") (pinfunction "GND_B18") (pintype "power_in"))
      (node (ref "D5") (pin "B2") (pinfunction "GND_B2") (pintype "power_in"))
      (node (ref "D5") (pin "B3") (pinfunction "GND_B3") (pintype "power_in"))
      (node (ref "D5") (pin "B4") (pinfunction "GND_B4") (pintype "power_in"))
      (node (ref "D5") (pin "B8") (pinfunction "GND_B8") (pintype "power_in"))
      (node (ref "D5") (pin "C1") (pinfunction "GND_C1") (pintype "power_in"))
      (node (ref "D5") (pin "C11") (pinfunction "GND_C11") (pintype "power_in"))
      (node (ref "D5") (pin "C2") (pinfunction "GND_C2") (pintype "power_in"))
      (node (ref "D5") (pin "C21") (pinfunction "GND_C21") (pintype "power_in"))
      (node (ref "D5") (pin "C5") (pinfunction "GND_C5") (pintype "power_in"))
      (node (ref "D5") (pin "C8") (pinfunction "VREFB8AN0_C8") (pintype "power_in"))
      (node (ref "D5") (pin "D1") (pinfunction "GND_D1") (pintype "power_in"))
      (node (ref "D5") (pin "D14") (pinfunction "GND_D14") (pintype "power_in"))
      (node (ref "D5") (pin "D2") (pinfunction "GND_D2") (pintype "power_in"))
      (node (ref "D5") (pin "D23") (pinfunction "GND_D23") (pintype "power_in"))
      (node (ref "D5") (pin "D24") (pinfunction "GND_D24") (pintype "power_in"))
      (node (ref "D5") (pin "D3") (pinfunction "GND_D3") (pintype "power_in"))
      (node (ref "D5") (pin "D4") (pinfunction "GND_D4") (pintype "power_in"))
      (node (ref "D5") (pin "D5") (pinfunction "nCE_D5") (pintype "input"))
      (node (ref "D5") (pin "E1") (pinfunction "GND_E1") (pintype "power_in"))
      (node (ref "D5") (pin "E17") (pinfunction "GND_E17") (pintype "power_in"))
      (node (ref "D5") (pin "E2") (pinfunction "GND_E2") (pintype "power_in"))
      (node (ref "D5") (pin "E5") (pinfunction "GND_E5") (pintype "power_in"))
      (node (ref "D5") (pin "E7") (pinfunction "GND_E7") (pintype "power_in"))
      (node (ref "D5") (pin "F1") (pinfunction "GND_F1") (pintype "power_in"))
      (node (ref "D5") (pin "F10") (pinfunction "GND_F10") (pintype "power_in"))
      (node (ref "D5") (pin "F2") (pinfunction "GND_F2") (pintype "power_in"))
      (node (ref "D5") (pin "F20") (pinfunction "GND_F20") (pintype "power_in"))
      (node (ref "D5") (pin "F3") (pinfunction "GND_F3") (pintype "power_in"))
      (node (ref "D5") (pin "F4") (pinfunction "GND_F4") (pintype "power_in"))
      (node (ref "D5") (pin "G1") (pinfunction "GND_G1") (pintype "power_in"))
      (node (ref "D5") (pin "G13") (pinfunction "GND_G13") (pintype "power_in"))
      (node (ref "D5") (pin "G2") (pinfunction "GND_G2") (pintype "power_in"))
      (node (ref "D5") (pin "G23") (pinfunction "GND_G23") (pintype "power_in"))
      (node (ref "D5") (pin "G5") (pinfunction "GND_G5") (pintype "power_in"))
      (node (ref "D5") (pin "H1") (pinfunction "GND_H1") (pintype "power_in"))
      (node (ref "D5") (pin "H16") (pinfunction "GND_H16") (pintype "power_in"))
      (node (ref "D5") (pin "H2") (pinfunction "GND_H2") (pintype "power_in"))
      (node (ref "D5") (pin "H26") (pinfunction "GND_H26") (pintype "power_in"))
      (node (ref "D5") (pin "H3") (pinfunction "GND_H3") (pintype "power_in"))
      (node (ref "D5") (pin "H4") (pinfunction "GND_H4") (pintype "power_in"))
      (node (ref "D5") (pin "H5") (pinfunction "GND_H5") (pintype "power_in"))
      (node (ref "D5") (pin "H6") (pinfunction "GND_H6") (pintype "power_in"))
      (node (ref "D5") (pin "J1") (pinfunction "GND_J1") (pintype "power_in"))
      (node (ref "D5") (pin "J14") (pinfunction "GND_J14") (pintype "power_in"))
      (node (ref "D5") (pin "J18") (pinfunction "GND_J18") (pintype "power_in"))
      (node (ref "D5") (pin "J2") (pinfunction "GND_J2") (pintype "power_in"))
      (node (ref "D5") (pin "J4") (pinfunction "GND_J4") (pintype "power_in"))
      (node (ref "D5") (pin "J9") (pinfunction "GND_J9") (pintype "power_in"))
      (node (ref "D5") (pin "K12") (pinfunction "GND_K12") (pintype "power_in"))
      (node (ref "D5") (pin "K13") (pinfunction "GND_K13") (pintype "power_in"))
      (node (ref "D5") (pin "K15") (pinfunction "GND_K15") (pintype "power_in"))
      (node (ref "D5") (pin "K17") (pinfunction "GND_K17") (pintype "power_in"))
      (node (ref "D5") (pin "K19") (pinfunction "GND_K19") (pintype "power_in"))
      (node (ref "D5") (pin "K22") (pinfunction "GND_K22") (pintype "power_in"))
      (node (ref "D5") (pin "K3") (pinfunction "GND_K3") (pintype "power_in"))
      (node (ref "D5") (pin "K5") (pinfunction "MSEL3_K5") (pintype "input"))
      (node (ref "D5") (pin "L1") (pinfunction "GND_L1") (pintype "power_in"))
      (node (ref "D5") (pin "L10") (pinfunction "GND_L10") (pintype "power_in"))
      (node (ref "D5") (pin "L14") (pinfunction "GND_L14") (pintype "power_in"))
      (node (ref "D5") (pin "L16") (pinfunction "GND_L16") (pintype "power_in"))
      (node (ref "D5") (pin "L18") (pinfunction "GND_L18") (pintype "power_in"))
      (node (ref "D5") (pin "L2") (pinfunction "GND_L2") (pintype "power_in"))
      (node (ref "D5") (pin "L20") (pinfunction "GND_L20") (pintype "power_in"))
      (node (ref "D5") (pin "L25") (pinfunction "GND_L25") (pintype "power_in"))
      (node (ref "D5") (pin "L26") (pinfunction "VREFB6AN0_L26") (pintype "power_in"))
      (node (ref "D5") (pin "L4") (pinfunction "GND_L4") (pintype "power_in"))
      (node (ref "D5") (pin "L5") (pinfunction "GND_L5") (pintype "power_in"))
      (node (ref "D5") (pin "L6") (pinfunction "MSEL1_L6") (pintype "input"))
      (node (ref "D5") (pin "M1") (pinfunction "GND_M1") (pintype "power_in"))
      (node (ref "D5") (pin "M13") (pinfunction "GND_M13") (pintype "power_in"))
      (node (ref "D5") (pin "M15") (pinfunction "GND_M15") (pintype "power_in"))
      (node (ref "D5") (pin "M17") (pinfunction "GND_M17") (pintype "power_in"))
      (node (ref "D5") (pin "M19") (pinfunction "GND_M19") (pintype "power_in"))
      (node (ref "D5") (pin "M2") (pinfunction "GND_M2") (pintype "power_in"))
      (node (ref "D5") (pin "M3") (pinfunction "GND_M3") (pintype "power_in"))
      (node (ref "D5") (pin "M5") (pinfunction "GND_M5") (pintype "power_in"))
      (node (ref "D5") (pin "M6") (pinfunction "GND_M6") (pintype "power_in"))
      (node (ref "D5") (pin "M8") (pinfunction "GND_M8") (pintype "power_in"))
      (node (ref "D5") (pin "N1") (pinfunction "GND_N1") (pintype "power_in"))
      (node (ref "D5") (pin "N11") (pinfunction "GND_N11") (pintype "power_in"))
      (node (ref "D5") (pin "N14") (pinfunction "GND_N14") (pintype "power_in"))
      (node (ref "D5") (pin "N16") (pinfunction "GND_N16") (pintype "power_in"))
      (node (ref "D5") (pin "N18") (pinfunction "GND_N18") (pintype "power_in"))
      (node (ref "D5") (pin "N2") (pinfunction "GND_N2") (pintype "power_in"))
      (node (ref "D5") (pin "N21") (pinfunction "GND_N21") (pintype "power_in"))
      (node (ref "D5") (pin "N4") (pinfunction "GND_N4") (pintype "power_in"))
      (node (ref "D5") (pin "N6") (pinfunction "GND_N6") (pintype "power_in"))
      (node (ref "D5") (pin "N7") (pinfunction "GND_N7") (pintype "power_in"))
      (node (ref "D5") (pin "P13") (pinfunction "GND_P13") (pintype "power_in"))
      (node (ref "D5") (pin "P15") (pinfunction "GND_P15") (pintype "power_in"))
      (node (ref "D5") (pin "P17") (pinfunction "GND_P17") (pintype "power_in"))
      (node (ref "D5") (pin "P19") (pinfunction "GND_P19") (pintype "power_in"))
      (node (ref "D5") (pin "P24") (pinfunction "GND_P24") (pintype "power_in"))
      (node (ref "D5") (pin "P25") (pinfunction "VREFB5BN0_P25") (pintype "power_in"))
      (node (ref "D5") (pin "P3") (pinfunction "GND_P3") (pintype "power_in"))
      (node (ref "D5") (pin "P5") (pinfunction "GND_P5") (pintype "power_in"))
      (node (ref "D5") (pin "P6") (pinfunction "GND_P6") (pintype "power_in"))
      (node (ref "D5") (pin "P7") (pinfunction "GND_P7") (pintype "power_in"))
      (node (ref "D5") (pin "P9") (pinfunction "GND_P9") (pintype "power_in"))
      (node (ref "D5") (pin "R1") (pinfunction "GND_R1") (pintype "power_in"))
      (node (ref "D5") (pin "R12") (pinfunction "GND_R12") (pintype "power_in"))
      (node (ref "D5") (pin "R14") (pinfunction "GND_R14") (pintype "power_in"))
      (node (ref "D5") (pin "R16") (pinfunction "GND_R16") (pintype "power_in"))
      (node (ref "D5") (pin "R18") (pinfunction "GND_R18") (pintype "power_in"))
      (node (ref "D5") (pin "R2") (pinfunction "GND_R2") (pintype "power_in"))
      (node (ref "D5") (pin "R4") (pinfunction "GND_R4") (pintype "power_in"))
      (node (ref "D5") (pin "R7") (pinfunction "GND_R7") (pintype "power_in"))
      (node (ref "D5") (pin "T1") (pinfunction "GND_T1") (pintype "power_in"))
      (node (ref "D5") (pin "T10") (pinfunction "GND_T10") (pintype "power_in"))
      (node (ref "D5") (pin "T15") (pinfunction "GND_T15") (pintype "power_in"))
      (node (ref "D5") (pin "T2") (pinfunction "GND_T2") (pintype "power_in"))
      (node (ref "D5") (pin "T20") (pinfunction "GND_T20") (pintype "power_in"))
      (node (ref "D5") (pin "T3") (pinfunction "GND_T3") (pintype "power_in"))
      (node (ref "D5") (pin "T5") (pinfunction "GND_T5") (pintype "power_in"))
      (node (ref "D5") (pin "U1") (pinfunction "GND_U1") (pintype "power_in"))
      (node (ref "D5") (pin "U13") (pinfunction "GND_U13") (pintype "power_in"))
      (node (ref "D5") (pin "U2") (pinfunction "GND_U2") (pintype "power_in"))
      (node (ref "D5") (pin "U23") (pinfunction "GND_U23") (pintype "power_in"))
      (node (ref "D5") (pin "U4") (pinfunction "GND_U4") (pintype "power_in"))
      (node (ref "D5") (pin "V1") (pinfunction "GND_V1") (pintype "power_in"))
      (node (ref "D5") (pin "V16") (pinfunction "GND_V16") (pintype "power_in"))
      (node (ref "D5") (pin "V2") (pinfunction "GND_V2") (pintype "power_in"))
      (node (ref "D5") (pin "V26") (pinfunction "GND_V26") (pintype "power_in"))
      (node (ref "D5") (pin "V3") (pinfunction "GND_V3") (pintype "power_in"))
      (node (ref "D5") (pin "V4") (pinfunction "GND_V4") (pintype "power_in"))
      (node (ref "D5") (pin "V5") (pinfunction "GND_V5") (pintype "power_in"))
      (node (ref "D5") (pin "V6") (pinfunction "GND_V6") (pintype "power_in"))
      (node (ref "D5") (pin "W1") (pinfunction "GND_W1") (pintype "power_in"))
      (node (ref "D5") (pin "W19") (pinfunction "GND_W19") (pintype "power_in"))
      (node (ref "D5") (pin "W2") (pinfunction "GND_W2") (pintype "power_in"))
      (node (ref "D5") (pin "W23") (pinfunction "VREFB5AN0_W23") (pintype "power_in"))
      (node (ref "D5") (pin "W5") (pinfunction "GND_W5") (pintype "power_in"))
      (node (ref "D5") (pin "W6") (pinfunction "GND_W6") (pintype "power_in"))
      (node (ref "D5") (pin "W9") (pinfunction "GND_W9") (pintype "power_in"))
      (node (ref "D5") (pin "Y1") (pinfunction "GND_Y1") (pintype "power_in"))
      (node (ref "D5") (pin "Y12") (pinfunction "GND_Y12") (pintype "power_in"))
      (node (ref "D5") (pin "Y2") (pinfunction "GND_Y2") (pintype "power_in"))
      (node (ref "D5") (pin "Y22") (pinfunction "GND_Y22") (pintype "power_in"))
      (node (ref "D5") (pin "Y3") (pinfunction "GND_Y3") (pintype "power_in"))
      (node (ref "D5") (pin "Y4") (pinfunction "GND_Y4") (pintype "power_in"))
      (node (ref "R84") (pin "1") (pinfunction "1_1") (pintype "passive"))
      (node (ref "X7") (pin "10") (pintype "passive"))
      (node (ref "X7") (pin "2") (pintype "passive"))
    )
    (net (code "2") (name "/Fpga_CONF_DONE") (class "Default")
      (node (ref "D5") (pin "A6") (pinfunction "CONF_DONE_A6") (pintype "bidirectional"))
      (node (ref "R82") (pin "2") (pinfunction "2_2") (pintype "passive"))
    )
    (net (code "3") (name "/Fpga_DCLK") (class "Default")
      (node (ref "D5") (pin "N8") (pinfunction "DCLK_N8") (pintype "bidirectional"))
      (node (ref "R83") (pin "2") (pinfunction "2_2") (pintype "passive"))
    )
    (net (code "4") (name "/Fpga_Data0") (class "Default")
      (node (ref "D5") (pin "AF5") (pinfunction "AS_DATA0,_ASDO,_DATA0_AF5") (pintype "bidirectional"))
    )
    (net (code "5") (name "/Fpga_nCONFIG") (class "Default")
      (node (ref "D5") (pin "F5") (pinfunction "nCONFIG_F5") (pintype "input"))
      (node (ref "R81") (pin "2") (pinfunction "2_2") (pintype "passive"))
    )
    (net (code "6") (name "/Fpga_nSTATUS") (class "Default")
      (node (ref "D5") (pin "B5") (pinfunction "nSTATUS_B5") (pintype "bidirectional"))
    )
    (net (code "7") (name "/TCK") (class "Default")
      (node (ref "D5") (pin "Y5") (pinfunction "TCK_Y5") (pintype "input"))
      (node (ref "R77") (pin "2") (pinfunction "2_2") (pintype "passive"))
      (node (ref "R84") (pin "2") (pinfunction "2_2") (pintype "passive"))
      (node (ref "X7") (pin "1") (pintype "passive"))
    )
    (net (code "8") (name "/TDI") (class "Default")
      (node (ref "D5") (pin "T6") (pinfunction "TDI_T6") (pintype "input"))
      (node (ref "R78") (pin "1") (pinfunction "1_1") (pintype "passive"))
      (node (ref "X7") (pin "9") (pintype "passive"))
    )
    (net (code "9") (name "/TDO") (class "Default")
      (node (ref "D5") (pin "V7") (pinfunction "TDO_V7") (pintype "output"))
      (node (ref "X7") (pin "3") (pintype "passive"))
    )
    (net (code "10") (name "/TMS") (class "Default")
      (node (ref "D5") (pin "R6") (pinfunction "TMS_R6") (pintype "input"))
      (node (ref "R76") (pin "2") (pinfunction "2_2") (pintype "passive"))
      (node (ref "X7") (pin "5") (pintype "passive"))
    )
    (net (code "11") (name "/v1p1d") (class "Default")
      (node (ref "C123") (pin "2") (pinfunction "2_2") (pintype "passive"))
      (node (ref "C124") (pin "2") (pinfunction "2_2") (pintype "passive"))
      (node (ref "C125") (pin "2") (pinfunction "2_2") (pintype "passive"))
      (node (ref "C126") (pin "2") (pinfunction "2_2") (pintype "passive"))
      (node (ref "C127") (pin "2") (pinfunction "2_2") (pintype "passive"))
      (node (ref "C128") (pin "2") (pinfunction "2_2") (pintype "passive"))
      (node (ref "C129") (pin "2") (pinfunction "2_2") (pintype "passive"))
      (node (ref "C135") (pin "2") (pinfunction "2_2") (pintype "passive"))
      (node (ref "C136") (pin "2") (pinfunction "2_2") (pintype "passive"))
      (node (ref "C137") (pin "2") (pinfunction "2_2") (pintype "passive"))
      (node (ref "C138") (pin "2") (pinfunction "2_2") (pintype "passive"))
      (node (ref "C139") (pin "2") (pinfunction "2_2") (pintype "passive"))
      (node (ref "C140") (pin "2") (pinfunction "2_2") (pintype "passive"))
      (node (ref "C141") (pin "2") (pinfunction "2_2") (pintype "passive"))
      (node (ref "C147") (pin "2") (pinfunction "2_2") (pintype "passive"))
      (node (ref "C148") (pin "2") (pinfunction "2_2") (pintype "passive"))
      (node (ref "C149") (pin "2") (pinfunction "2_2") (pintype "passive"))
      (node (ref "C150") (pin "2") (pinfunction "2_2") (pintype "passive"))
      (node (ref "C151") (pin "2") (pinfunction "2_2") (pintype "passive"))
      (node (ref "C152") (pin "2") (pinfunction "2_2") (pintype "passive"))
      (node (ref "C153") (pin "2") (pinfunction "2_2") (pintype "passive"))
      (node (ref "C154") (pin "2") (pinfunction "2_2") (pintype "passive"))
      (node (ref "D5") (pin "J13") (pinfunction "VCC_J13") (pintype "power_in"))
      (node (ref "D5") (pin "J15") (pinfunction "VCC_J15") (pintype "power_in"))
      (node (ref "D5") (pin "J17") (pinfunction "VCC_J17") (pintype "power_in"))
      (node (ref "D5") (pin "J19") (pinfunction "VCC_J19") (pintype "power_in"))
      (node (ref "D5") (pin "J3") (pinfunction "VCC_J3") (pintype "power_in"))
      (node (ref "D5") (pin "K14") (pinfunction "VCC_K14") (pintype "power_in"))
      (node (ref "D5") (pin "K16") (pinfunction "VCC_K16") (pintype "power_in"))
      (node (ref "D5") (pin "K18") (pinfunction "VCC_K18") (pintype "power_in"))
      (node (ref "D5") (pin "K20") (pinfunction "VCC_K20") (pintype "power_in"))
      (node (ref "D5") (pin "K4") (pinfunction "VCC_K4") (pintype "power_in"))
      (node (ref "D5") (pin "L13") (pinfunction "VCC_L13") (pintype "power_in"))
      (node (ref "D5") (pin "L15") (pinfunction "VCC_L15") (pintype "power_in"))
      (node (ref "D5") (pin "L17") (pinfunction "VCC_L17") (pintype "power_in"))
      (node (ref "D5") (pin "L19") (pinfunction "VCC_L19") (pintype "power_in"))
      (node (ref "D5") (pin "M14") (pinfunction "VCC_M14") (pintype "power_in"))
      (node (ref "D5") (pin "M16") (pinfunction "VCC_M16") (pintype "power_in"))
      (node (ref "D5") (pin "M18") (pinfunction "VCC_M18") (pintype "power_in"))
      (node (ref "D5") (pin "M20") (pinfunction "VCC_M20") (pintype "power_in"))
      (node (ref "D5") (pin "M4") (pinfunction "VCC_M4") (pintype "power_in"))
      (node (ref "D5") (pin "N13") (pinfunction "VCC_N13") (pintype "power_in"))
      (node (ref "D5") (pin "N15") (pinfunction "VCC_N15") (pintype "power_in"))
      (node (ref "D5") (pin "N17") (pinfunction "VCC_N17") (pintype "power_in"))
      (node (ref "D5") (pin "N19") (pinfunction "VCC_N19") (pintype "power_in"))
      (node (ref "D5") (pin "N3") (pinfunction "VCC_N3") (pintype "power_in"))
      (node (ref "D5") (pin "N5") (pinfunction "VCC_N5") (pintype "power_in"))
      (node (ref "D5") (pin "P14") (pinfunction "VCC_P14") (pintype "power_in"))
      (node (ref "D5") (pin "P16") (pinfunction "VCC_P16") (pintype "power_in"))
      (node (ref "D5") (pin "P18") (pinfunction "VCC_P18") (pintype "power_in"))
      (node (ref "D5") (pin "P4") (pinfunction "VCC_P4") (pintype "power_in"))
      (node (ref "D5") (pin "R13") (pinfunction "VCC_R13") (pintype "power_in"))
      (node (ref "D5") (pin "R15") (pinfunction "VCC_R15") (pintype "power_in"))
      (node (ref "D5") (pin "R17") (pinfunction "VCC_R17") (pintype "power_in"))
      (node (ref "D5") (pin "R19") (pinfunction "VCC_R19") (pintype "power_in"))
      (node (ref "D5") (pin "R5") (pinfunction "VCC_R5") (pintype "power_in"))
      (node (ref "D5") (pin "T14") (pinfunction "VCC_T14") (pintype "power_in"))
      (node (ref "D5") (pin "T16") (pinfunction "VCC_T16") (pintype "power_in"))
      (node (ref "D5") (pin "T18") (pinfunction "VCC_T18") (pintype "power_in"))
      (node (ref "D5") (pin "U3") (pinfunction "VCC_U3") (pintype "power_in"))
      (node (ref "D5") (pin "U5") (pinfunction "VCC_U5") (pintype "power_in"))
    )
    (net (code "12") (name "/v1p5d") (class "Default")
      (node (ref "C173") (pin "2") (pinfunction "2_2") (pintype "passive"))
      (node (ref "C174") (pin "2") (pinfunction "2_2") (pintype "passive"))
      (node (ref "C175") (pin "2") (pinfunction "2_2") (pintype "passive"))
      (node (ref "C176") (pin "2") (pinfunction "2_2") (pintype "passive"))
      (node (ref "C177") (pin "2") (pinfunction "2_2") (pintype "passive"))
      (node (ref "C178") (pin "2") (pinfunction "2_2") (pintype "passive"))
      (node (ref "C179") (pin "2") (pinfunction "2_2") (pintype "passive"))
      (node (ref "D5") (pin "AA10") (pinfunction "VCCIO3B_AA10") (pintype "power_in"))
      (node (ref "D5") (pin "AA20") (pinfunction "VCCIO4A_AA20") (pintype "power_in"))
      (node (ref "D5") (pin "AB13") (pinfunction "VCCIO4A_AB13") (pintype "power_in"))
      (node (ref "D5") (pin "AC16") (pinfunction "VCCIO4A_AC16") (pintype "power_in"))
      (node (ref "D5") (pin "AD19") (pinfunction "VCCIO4A_AD19") (pintype "power_in"))
      (node (ref "D5") (pin "AD9") (pinfunction "VCCIO3B_AD9") (pintype "power_in"))
      (node (ref "D5") (pin "AE12") (pinfunction "VCCIO4A_AE12") (pintype "power_in"))
      (node (ref "D5") (pin "AE22") (pinfunction "VCCIO4A_AE22") (pintype "power_in"))
      (node (ref "D5") (pin "AF15") (pinfunction "VCCIO4A_AF15") (pintype "power_in"))
      (node (ref "D5") (pin "E8") (pinfunction "VCCBAT_E8") (pintype "power_in"))
      (node (ref "D5") (pin "U18") (pinfunction "VCCIO4A_U18") (pintype "power_in"))
      (node (ref "D5") (pin "U8") (pinfunction "VCCIO3B_U8") (pintype "power_in"))
      (node (ref "D5") (pin "V11") (pinfunction "VCCIO3B_V11") (pintype "power_in"))
      (node (ref "D5") (pin "W14") (pinfunction "VCCIO4A_W14") (pintype "power_in"))
      (node (ref "D5") (pin "Y17") (pinfunction "VCCIO4A_Y17") (pintype "power_in"))
    )
    (net (code "13") (name "/v1p8d") (class "Default")
      (node (ref "C180") (pin "2") (pinfunction "2_2") (pintype "passive"))
      (node (ref "C181") (pin "2") (pinfunction "2_2") (pintype "passive"))
      (node (ref "C189") (pin "2") (pinfunction "2_2") (pintype "passive"))
      (node (ref "C190") (pin "2") (pinfunction "2_2") (pintype "passive"))
      (node (ref "C191") (pin "2") (pinfunction "2_2") (pintype "passive"))
      (node (ref "C192") (pin "2") (pinfunction "2_2") (pintype "passive"))
      (node (ref "C197") (pin "2") (pinfunction "2_2") (pintype "passive"))
      (node (ref "C198") (pin "2") (pinfunction "2_2") (pintype "passive"))
      (node (ref "C199") (pin "2") (pinfunction "2_2") (pintype "passive"))
      (node (ref "C200") (pin "2") (pinfunction "2_2") (pintype "passive"))
      (node (ref "D5") (pin "AB23") (pinfunction "VCCIO5A_AB23") (pintype "power_in"))
      (node (ref "D5") (pin "C26") (pinfunction "VCCIO6A_C26") (pintype "power_in"))
      (node (ref "D5") (pin "E22") (pinfunction "VCCIO6A_E22") (pintype "power_in"))
      (node (ref "D5") (pin "F25") (pinfunction "VCCIO6A_F25") (pintype "power_in"))
      (node (ref "D5") (pin "H21") (pinfunction "VCCIO6A_H21") (pintype "power_in"))
      (node (ref "D5") (pin "J24") (pinfunction "VCCIO6A_J24") (pintype "power_in"))
      (node (ref "D5") (pin "M23") (pinfunction "VCCIO6A_M23") (pintype "power_in"))
      (node (ref "D5") (pin "N26") (pinfunction "VCCIO5B_N26") (pintype "power_in"))
      (node (ref "D5") (pin "R22") (pinfunction "VCCIO5B_R22") (pintype "power_in"))
      (node (ref "D5") (pin "T25") (pinfunction "VCCIO5B_T25") (pintype "power_in"))
      (node (ref "D5") (pin "V21") (pinfunction "VCCIO5A_V21") (pintype "power_in"))
      (node (ref "D5") (pin "W24") (pinfunction "VCCIO5B_W24") (pintype "power_in"))
      (node (ref "L12") (pin "2") (pinfunction "2_2") (pintype "passive"))
    )
    (net (code "14") (name "/v2p5d") (class "Default")
      (node (ref "C157") (pin "2") (pinfunction "2_2") (pintype "passive"))
      (node (ref "C158") (pin "2") (pinfunction "2_2") (pintype "passive"))
      (node (ref "C159") (pin "2") (pinfunction "2_2") (pintype "passive"))
      (node (ref "C160") (pin "2") (pinfunction "2_2") (pintype "passive"))
      (node (ref "C161") (pin "2") (pinfunction "2_2") (pintype "passive"))
      (node (ref "C162") (pin "2") (pinfunction "2_2") (pintype "passive"))
      (node (ref "C163") (pin "2") (pinfunction "2_2") (pintype "passive"))
      (node (ref "C164") (pin "2") (pinfunction "2_2") (pintype "passive"))
      (node (ref "C165") (pin "2") (pinfunction "2_2") (pintype "passive"))
      (node (ref "C166") (pin "2") (pinfunction "2_2") (pintype "passive"))
      (node (ref "C167") (pin "2") (pinfunction "2_2") (pintype "passive"))
      (node (ref "C168") (pin "2") (pinfunction "2_2") (pintype "passive"))
      (node (ref "C182") (pin "2") (pinfunction "2_2") (pintype "passive"))
      (node (ref "C183") (pin "2") (pinfunction "2_2") (pintype "passive"))
      (node (ref "C184") (pin "2") (pinfunction "2_2") (pintype "passive"))
      (node (ref "C185") (pin "2") (pinfunction "2_2") (pintype "passive"))
      (node (ref "C186") (pin "2") (pinfunction "2_2") (pintype "passive"))
      (node (ref "C187") (pin "2") (pinfunction "2_2") (pintype "passive"))
      (node (ref "C188") (pin "2") (pinfunction "2_2") (pintype "passive"))
      (node (ref "D5") (pin "A10") (pinfunction "VCCIO7A_A10") (pintype "power_in"))
      (node (ref "D5") (pin "A20") (pinfunction "VCCIO7A_A20") (pintype "power_in"))
      (node (ref "D5") (pin "AA11") (pinfunction "VCCPD3B4A_AA11") (pintype "power_in"))
      (node (ref "D5") (pin "AA13") (pinfunction "VCCPD3B4A_AA13") (pintype "power_in"))
      (node (ref "D5") (pin "AA17") (pinfunction "VCCPD3B4A_AA17") (pintype "power_in"))
      (node (ref "D5") (pin "AA19") (pinfunction "VCCPD3B4A_AA19") (pintype "power_in"))
      (node (ref "D5") (pin "AB21") (pinfunction "VCCPD3B4A_AB21") (pintype "power_in"))
      (node (ref "D5") (pin "AB9") (pinfunction "VCCPD3A_AB9") (pintype "power_in"))
      (node (ref "D5") (pin "B13") (pinfunction "VCCIO7A_B13") (pintype "power_in"))
      (node (ref "D5") (pin "B23") (pinfunction "VCCIO7A_B23") (pintype "power_in"))
      (node (ref "D5") (pin "C16") (pinfunction "VCCIO7A_C16") (pintype "power_in"))
      (node (ref "D5") (pin "D19") (pinfunction "VCCIO7A_D19") (pintype "power_in"))
      (node (ref "D5") (pin "E12") (pinfunction "VCCIO7A_E12") (pintype "power_in"))
      (node (ref "D5") (pin "F11") (pinfunction "VCCPD7A8A_F11") (pintype "power_in"))
      (node (ref "D5") (pin "F13") (pinfunction "VCCPD7A8A_F13") (pintype "power_in"))
      (node (ref "D5") (pin "F15") (pinfunction "VCCIO7A_F15") (pintype "power_in"))
      (node (ref "D5") (pin "F17") (pinfunction "VCCPD7A8A_F17") (pintype "power_in"))
      (node (ref "D5") (pin "F19") (pinfunction "VCCPD7A8A_F19") (pintype "power_in"))
      (node (ref "D5") (pin "F9") (pinfunction "VCCPD7A8A_F9") (pintype "power_in"))
      (node (ref "D5") (pin "G18") (pinfunction "VCCIO7A_G18") (pintype "power_in"))
      (node (ref "D5") (pin "H11") (pinfunction "VCCIO7A_H11") (pintype "power_in"))
      (node (ref "D5") (pin "J22") (pinfunction "VCCPD6A_J22") (pintype "power_in"))
      (node (ref "D5") (pin "L21") (pinfunction "VCCPD6A_L21") (pintype "power_in"))
      (node (ref "D5") (pin "N22") (pinfunction "VCCPD5B_N22") (pintype "power_in"))
      (node (ref "D5") (pin "R21") (pinfunction "VCCPD5B_R21") (pintype "power_in"))
      (node (ref "D5") (pin "U21") (pinfunction "VCCPD5A_U21") (pintype "power_in"))
      (node (ref "L10") (pin "2") (pinfunction "2_2") (pintype "passive"))
      (node (ref "L11") (pin "2") (pinfunction "2_2") (pintype "passive"))
    )
    (net (code "15") (name "/v3p3d") (class "Default")
      (node (ref "C193") (pin "2") (pinfunction "2_2") (pintype "passive"))
      (node (ref "C194") (pin "2") (pinfunction "2_2") (pintype "passive"))
      (node (ref "C195") (pin "2") (pinfunction "2_2") (pintype "passive"))
      (node (ref "C196") (pin "2") (pinfunction "2_2") (pintype "passive"))
      (node (ref "D5") (pin "C6") (pinfunction "VCCIO8A_C6") (pintype "power_in"))
      (node (ref "D5") (pin "D9") (pinfunction "VCCIO8A_D9") (pintype "power_in"))
      (node (ref "D5") (pin "G8") (pinfunction "VCCIO8A_G8") (pintype "power_in"))
      (node (ref "D5") (pin "K7") (pinfunction "VCCIO8A_K7") (pintype "power_in"))
    )
    (net (code "16") (name "/vRefDDR") (class "Default")
      (node (ref "C171") (pin "2") (pinfunction "2_2") (pintype "passive"))
      (node (ref "C172") (pin "2") (pinfunction "2_2") (pintype "passive"))
      (node (ref "D5") (pin "AC12") (pinfunction "VREFB3BN0_AC12") (pintype "power_in"))
      (node (ref "D5") (pin "AD15") (pinfunction "VREFB4AN0_AD15") (pintype "power_in"))
    )
    (net (code "17") (name "/vcc_aux") (class "Default")
      (node (ref "C142") (pin "2") (pinfunction "2_2") (pintype "passive"))
      (node (ref "C143") (pin "2") (pinfunction "2_2") (pintype "passive"))
      (node (ref "C144") (pin "2") (pinfunction "2_2") (pintype "passive"))
      (node (ref "C145") (pin "2") (pinfunction "2_2") (pintype "passive"))
      (node (ref "C146") (pin "2") (pinfunction "2_2") (pintype "passive"))
      (node (ref "D5") (pin "AA8") (pinfunction "VCC_AUX_AA8") (pintype "power_in"))
      (node (ref "D5") (pin "AB14") (pinfunction "VCC_AUX_AB14") (pintype "power_in"))
      (node (ref "D5") (pin "AB20") (pinfunction "VCC_AUX_AB20") (pintype "power_in"))
      (node (ref "D5") (pin "E14") (pinfunction "VCC_AUX_E14") (pintype "power_in"))
      (node (ref "D5") (pin "G19") (pinfunction "VCC_AUX_G19") (pintype "power_in"))
      (node (ref "D5") (pin "G9") (pinfunction "VCC_AUX_G9") (pintype "power_in"))
      (node (ref "L11") (pin "1") (pinfunction "1_1") (pintype "passive"))
    )
    (net (code "18") (name "/vccpgm") (class "Default")
      (node (ref "C155") (pin "2") (pinfunction "2_2") (pintype "passive"))
      (node (ref "C156") (pin "2") (pinfunction "2_2") (pintype "passive"))
      (node (ref "C169") (pin "2") (pinfunction "2_2") (pintype "passive"))
      (node (ref "C170") (pin "2") (pinfunction "2_2") (pintype "passive"))
      (node (ref "D5") (pin "AA9") (pinfunction "VCCPGM_AA9") (pintype "power_in"))
      (node (ref "D5") (pin "AC6") (pinfunction "VCCIO3A_AC6") (pintype "power_in"))
      (node (ref "D5") (pin "F8") (pinfunction "VCCPGM_F8") (pintype "power_in"))
      (node (ref "D5") (pin "W22") (pinfunction "VCCPGM_W22") (pintype "power_in"))
      (node (ref "D5") (pin "Y7") (pinfunction "VCCIO3A_Y7") (pintype "power_in"))
      (node (ref "L12") (pin "1") (pinfunction "1_1") (pintype "passive"))
      (node (ref "R76") (pin "1") (pinfunction "1_1") (pintype "passive"))
      (node (ref "R77") (pin "1") (pinfunction "1_1") (pintype "passive"))
      (node (ref "R78") (pin "2") (pinfunction "2_2") (pintype "passive"))
      (node (ref "R79") (pin "2") (pinfunction "2_2") (pintype "passive"))
      (node (ref "R80") (pin "2") (pinfunction "2_2") (pintype "passive"))
      (node (ref "R81") (pin "1") (pinfunction "1_1") (pintype "passive"))
      (node (ref "R82") (pin "1") (pinfunction "1_1") (pintype "passive"))
      (node (ref "R83") (pin "1") (pinfunction "1_1") (pintype "passive"))
      (node (ref "X7") (pin "4") (pintype "passive"))
    )
    (net (code "19") (name "Net-(C130-Pad2)") (class "Default")
      (node (ref "C130") (pin "2") (pinfunction "2_2") (pintype "passive"))
      (node (ref "C131") (pin "2") (pinfunction "2_2") (pintype "passive"))
      (node (ref "C132") (pin "2") (pinfunction "2_2") (pintype "passive"))
      (node (ref "C133") (pin "2") (pinfunction "2_2") (pintype "passive"))
      (node (ref "C134") (pin "2") (pinfunction "2_2") (pintype "passive"))
      (node (ref "D5") (pin "G21") (pinfunction "VCCA_FPLL_G21") (pintype "power_in"))
      (node (ref "D5") (pin "J6") (pinfunction "VCCA_FPLL_J6") (pintype "power_in"))
      (node (ref "D5") (pin "L3") (pinfunction "VCCA_FPLL_L3") (pintype "power_in"))
      (node (ref "D5") (pin "R3") (pinfunction "VCCA_FPLL_R3") (pintype "power_in"))
      (node (ref "D5") (pin "T4") (pinfunction "VCCA_FPLL_T4") (pintype "power_in"))
      (node (ref "D5") (pin "W7") (pinfunction "VCCA_FPLL_W7") (pintype "power_in"))
      (node (ref "D5") (pin "Y21") (pinfunction "VCCA_FPLL_Y21") (pintype "power_in"))
      (node (ref "L10") (pin "1") (pinfunction "1_1") (pintype "passive"))
    )
    (net (code "20") (name "Net-(D5I-MSEL0)") (class "Default")
      (node (ref "D5") (pin "M7") (pinfunction "MSEL0_M7") (pintype "input"))
      (node (ref "R79") (pin "1") (pinfunction "1_1") (pintype "passive"))
    )
    (net (code "21") (name "Net-(D5I-MSEL4)") (class "Default")
      (node (ref "D5") (pin "J5") (pinfunction "MSEL4_J5") (pintype "input"))
      (node (ref "R80") (pin "1") (pinfunction "1_1") (pintype "passive"))
    )
    (net (code "22") (name "unconnected-(D5I-AS_DATA1,_DATA1-PadAD5)") (class "Default")
      (node (ref "D5") (pin "AD5") (pinfunction "AS_DATA1,_DATA1_AD5") (pintype "bidirectional"))
    )
    (net (code "23") (name "unconnected-(D5I-AS_DATA2,_DATA2-PadAB5)") (class "Default")
      (node (ref "D5") (pin "AB5") (pinfunction "AS_DATA2,_DATA2_AB5") (pintype "bidirectional"))
    )
    (net (code "24") (name "unconnected-(D5I-AS_DATA3,_DATA3-PadU6)") (class "Default")
      (node (ref "D5") (pin "U6") (pinfunction "AS_DATA3,_DATA3_U6") (pintype "bidirectional"))
    )
    (net (code "25") (name "unconnected-(D5I-nCSO,_DATA4-PadY6)") (class "Default")
      (node (ref "D5") (pin "Y6") (pinfunction "nCSO,_DATA4_Y6") (pintype "output"))
    )
    (net (code "26") (name "unconnected-(X7-Pad6)") (class "Default")
      (node (ref "X7") (pin "6") (pintype "passive"))
    )
    (net (code "27") (name "unconnected-(X7-Pad7)") (class "Default")
      (node (ref "X7") (pin "7") (pintype "passive"))
    )
    (net (code "28") (name "unconnected-(X7-Pad8)") (class "Default")
      (node (ref "X7") (pin "8") (pintype "passive"))
    )
  )
)
